# rtc.net
KiCad netlist of a schematic drawn in EAGLE
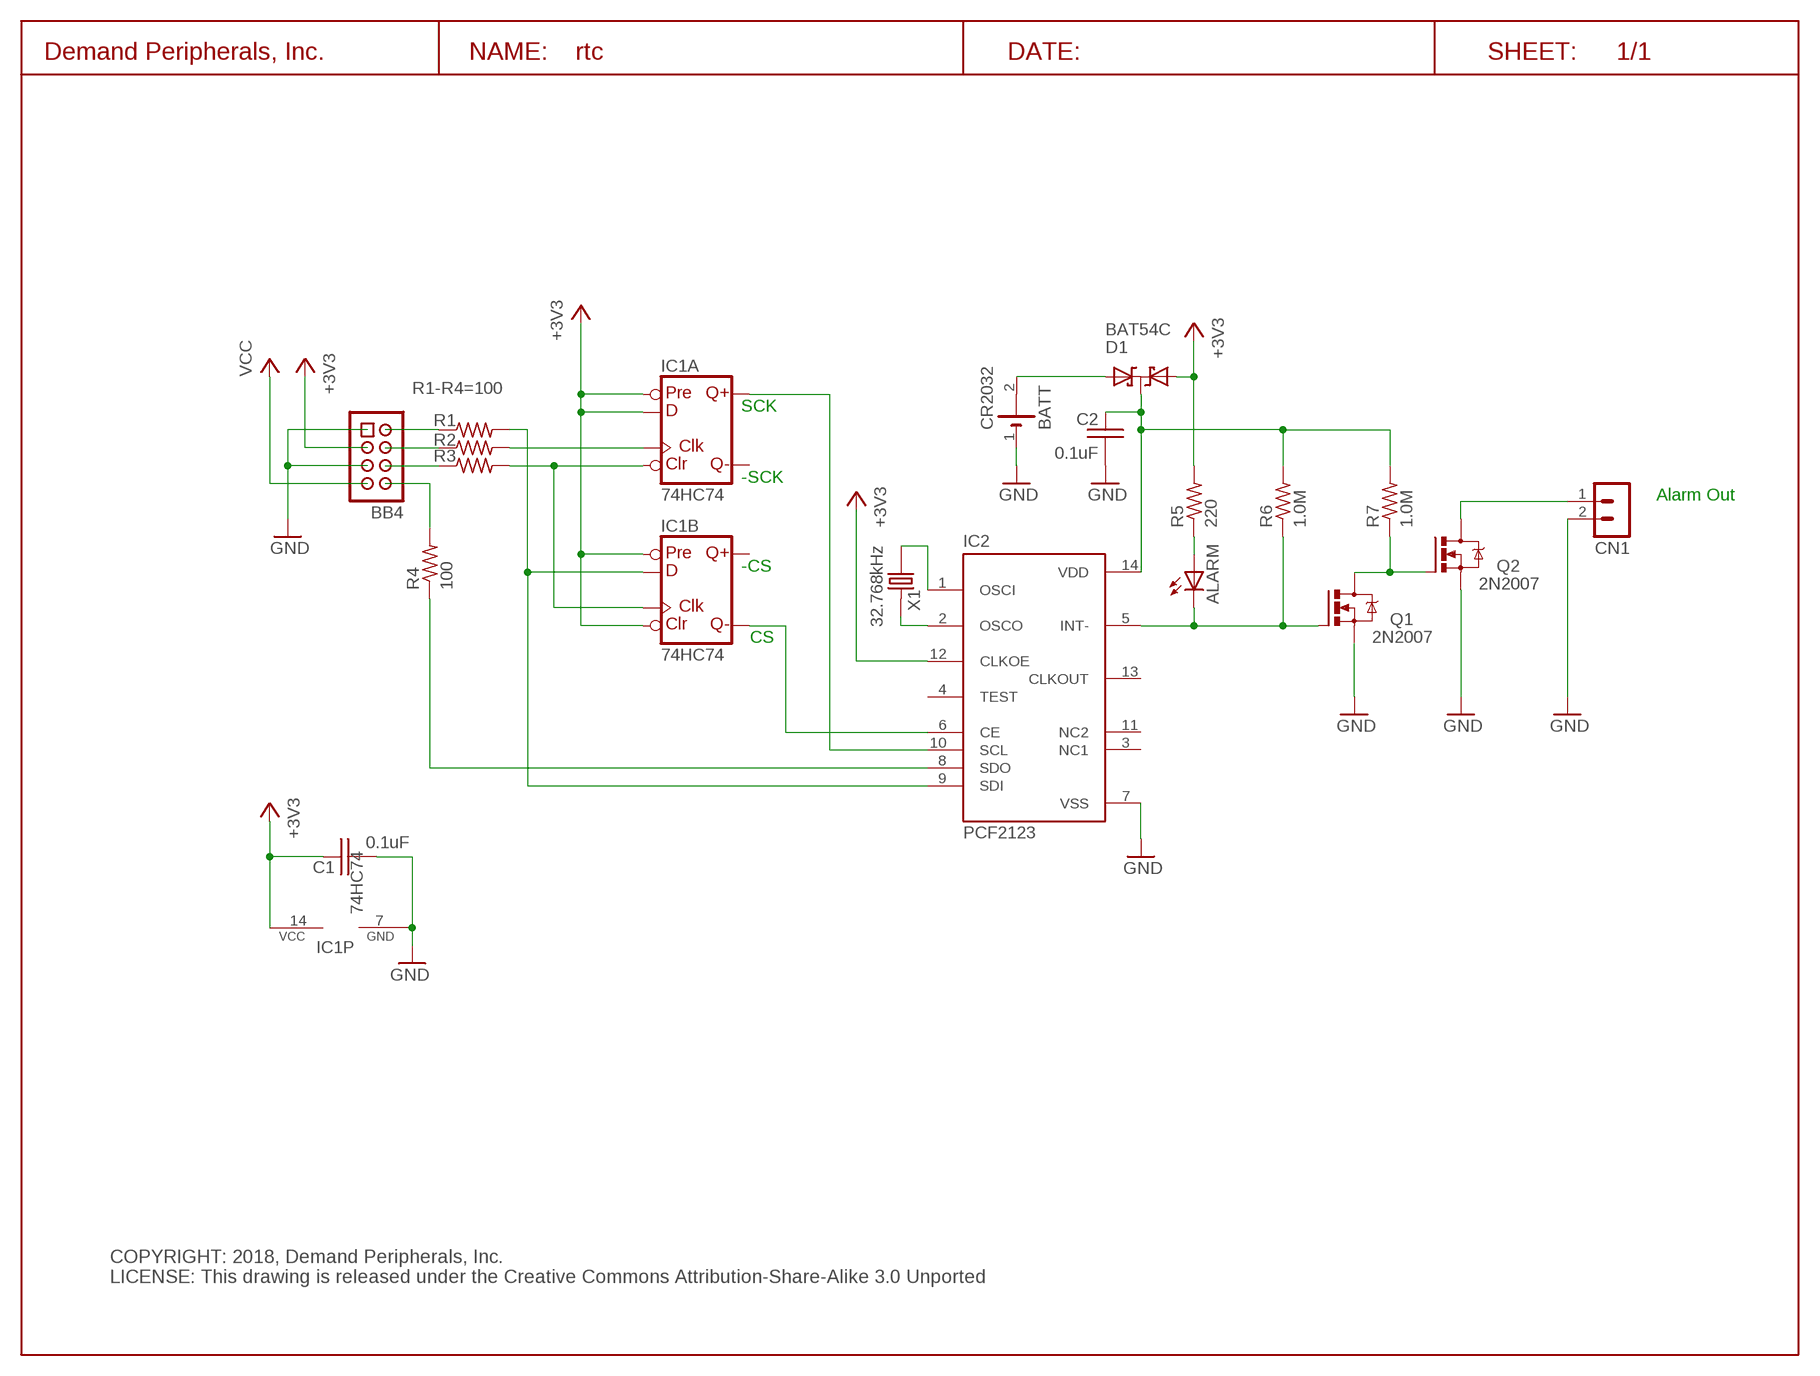
[diagram p0: schematic, sheet 1]

(export (version "E")
  (design (tool "Eeschema 10.0.6"))
  (components
    (comp (ref "ALARM")
      (value "Red_LED")
      (footprint "eagle-import:0805")
      (libsource (lib "eagle-import") (part "LED-0805-RED"))
    )
    (comp (ref "BATT")
      (value "CR2032")
      (footprint "eagle-import:CR2032_KEYSTONE")
      (libsource (lib "eagle-import") (part "CR2032_KEYSTONE"))
    )
    (comp (ref "BB4")
      (value "BB_CON")
      (footprint "eagle-import:HDR-4X2")
      (libsource (lib "eagle-import") (part "HDR-4X2-SHR"))
    )
    (comp (ref "C1")
      (value "0.1uF")
      (footprint "eagle-import:C0603")
      (libsource (lib "eagle-import") (part "C0.1UF_C0603"))
    )
    (comp (ref "C2")
      (value "0.1uF")
      (footprint "eagle-import:C0603")
      (libsource (lib "eagle-import") (part "C0.1UF_C0603"))
    )
    (comp (ref "CN1")
      (value "HDR-2X1-LCK")
      (footprint "eagle-import:HDR-2X1")
      (libsource (lib "eagle-import") (part "HDR-2X1-LCK"))
    )
    (comp (ref "D1")
      (value "BAT54C")
      (footprint "eagle-import:SOT23")
      (libsource (lib "eagle-import") (part "BAT54C"))
    )
    (comp (ref "IC1")
      (value "74HC74")
      (footprint "eagle-import:SO14")
      (libsource (lib "eagle-import") (part "74AHC74SS"))
    )
    (comp (ref "IC2")
      (value "PCF2123")
      (footprint "eagle-import:TSSOP14")
      (libsource (lib "eagle-import") (part "PCF2123"))
    )
    (comp (ref "Q1")
      (value "2N2007")
      (footprint "eagle-import:SOT23")
      (libsource (lib "eagle-import") (part "2N7002L"))
    )
    (comp (ref "Q2")
      (value "2N2007")
      (footprint "eagle-import:SOT23")
      (libsource (lib "eagle-import") (part "2N7002L"))
    )
    (comp (ref "R1")
      (value "100")
      (footprint "eagle-import:R0603")
      (libsource (lib "eagle-import") (part "R100_R0603"))
    )
    (comp (ref "R2")
      (value "100")
      (footprint "eagle-import:R0603")
      (libsource (lib "eagle-import") (part "R100_R0603"))
    )
    (comp (ref "R3")
      (value "100")
      (footprint "eagle-import:R0603")
      (libsource (lib "eagle-import") (part "R100_R0603"))
    )
    (comp (ref "R4")
      (value "100")
      (footprint "eagle-import:R0603")
      (libsource (lib "eagle-import") (part "R100_R0603"))
    )
    (comp (ref "R5")
      (value "220")
      (footprint "eagle-import:R0603")
      (libsource (lib "eagle-import") (part "R220_R0603"))
    )
    (comp (ref "R6")
      (value "1.0M")
      (footprint "eagle-import:R0603")
      (libsource (lib "eagle-import") (part "R1M_R0603"))
    )
    (comp (ref "R7")
      (value "1.0M")
      (footprint "eagle-import:R0603")
      (libsource (lib "eagle-import") (part "R1M_R0603"))
    )
    (comp (ref "U$1")
      (value "DP_FRAME_L")
      (footprint "eagle-import:LETTER_L")
      (libsource (lib "eagle-import") (part "DP_FRAME_L"))
    )
    (comp (ref "X1")
      (value "32.768kHz")
      (footprint "eagle-import:4-SOJ")
      (libsource (lib "eagle-import") (part "CRYSTAL-32.768"))
    )
  )
  (nets
    (net (code "1") (name "+3V3") (class "Default")
      (node (ref "BB4") (pin "3") (pinfunction "3_3") (pintype "passive"))
      (node (ref "C1") (pin "1") (pinfunction "1_1") (pintype "passive"))
      (node (ref "D1") (pin "2") (pinfunction "A_2") (pintype "passive"))
      (node (ref "IC1") (pin "10") (pinfunction "PRE_10") (pintype "input"))
      (node (ref "IC1") (pin "13") (pinfunction "CLR_13") (pintype "input"))
      (node (ref "IC1") (pin "14") (pinfunction "VCC_14") (pintype "power_in"))
      (node (ref "IC1") (pin "2") (pinfunction "D_2") (pintype "input"))
      (node (ref "IC1") (pin "4") (pinfunction "PRE_4") (pintype "input"))
      (node (ref "IC2") (pin "12") (pinfunction "CLKOE_12") (pintype "input"))
      (node (ref "R5") (pin "2") (pinfunction "2_2") (pintype "passive"))
    )
    (net (code "2") (name "GND") (class "Default")
      (node (ref "BATT") (pin "1") (pinfunction "-_1") (pintype "passive"))
      (node (ref "BB4") (pin "1") (pinfunction "1_1") (pintype "passive"))
      (node (ref "BB4") (pin "5") (pinfunction "5_5") (pintype "passive"))
      (node (ref "C1") (pin "2") (pinfunction "2_2") (pintype "passive"))
      (node (ref "C2") (pin "2") (pinfunction "2_2") (pintype "passive"))
      (node (ref "CN1") (pin "2") (pinfunction "1_2") (pintype "passive"))
      (node (ref "IC1") (pin "7") (pinfunction "GND_7") (pintype "power_in"))
      (node (ref "IC2") (pin "7") (pinfunction "VSS_7") (pintype "power_in"))
      (node (ref "Q1") (pin "3") (pinfunction "S_3") (pintype "passive"))
      (node (ref "Q2") (pin "3") (pinfunction "S_3") (pintype "passive"))
    )
    (net (code "3") (name "Net-(ALARM-PadA)") (class "Default")
      (node (ref "ALARM") (pin "A") (pinfunction "A_A") (pintype "passive"))
      (node (ref "R5") (pin "1") (pinfunction "1_1") (pintype "passive"))
    )
    (net (code "4") (name "Net-(BB4-Pad2)") (class "Default")
      (node (ref "BB4") (pin "2") (pinfunction "2_2") (pintype "passive"))
      (node (ref "R1") (pin "1") (pinfunction "1_1") (pintype "passive"))
    )
    (net (code "5") (name "Net-(BB4-Pad4)") (class "Default")
      (node (ref "BB4") (pin "4") (pinfunction "4_4") (pintype "passive"))
      (node (ref "R2") (pin "1") (pinfunction "1_1") (pintype "passive"))
    )
    (net (code "6") (name "Net-(BB4-Pad6)") (class "Default")
      (node (ref "BB4") (pin "6") (pinfunction "6_6") (pintype "passive"))
      (node (ref "R3") (pin "1") (pinfunction "1_1") (pintype "passive"))
    )
    (net (code "7") (name "Net-(BB4-Pad8)") (class "Default")
      (node (ref "BB4") (pin "8") (pinfunction "8_8") (pintype "passive"))
      (node (ref "R4") (pin "2") (pinfunction "2_2") (pintype "passive"))
    )
    (net (code "8") (name "Net-(CN1-2)") (class "Default")
      (node (ref "CN1") (pin "1") (pinfunction "2_1") (pintype "passive"))
      (node (ref "Q2") (pin "2") (pinfunction "D_2") (pintype "passive"))
    )
    (net (code "9") (name "Net-(D1-A1)") (class "Default")
      (node (ref "BATT") (pin "2") (pinfunction "+_2") (pintype "passive"))
      (node (ref "D1") (pin "1") (pinfunction "A1_1") (pintype "passive"))
    )
    (net (code "10") (name "Net-(D1-CC)") (class "Default")
      (node (ref "C2") (pin "1") (pinfunction "1_1") (pintype "passive"))
      (node (ref "D1") (pin "3") (pinfunction "CC_3") (pintype "passive"))
      (node (ref "IC2") (pin "14") (pinfunction "VDD_14") (pintype "power_in"))
      (node (ref "R6") (pin "2") (pinfunction "2_2") (pintype "passive"))
      (node (ref "R7") (pin "2") (pinfunction "2_2") (pintype "passive"))
    )
    (net (code "11") (name "Net-(IC1A-CLK)") (class "Default")
      (node (ref "IC1") (pin "3") (pinfunction "CLK_3") (pintype "input"))
      (node (ref "R2") (pin "2") (pinfunction "2_2") (pintype "passive"))
    )
    (net (code "12") (name "Net-(IC1A-CLR)") (class "Default")
      (node (ref "IC1") (pin "1") (pinfunction "CLR_1") (pintype "input"))
      (node (ref "IC1") (pin "11") (pinfunction "CLK_11") (pintype "input"))
      (node (ref "R3") (pin "2") (pinfunction "2_2") (pintype "passive"))
    )
    (net (code "13") (name "Net-(IC1A-Q)") (class "Default")
      (node (ref "IC1") (pin "5") (pinfunction "Q_5") (pintype "output"))
      (node (ref "IC2") (pin "10") (pinfunction "SCL_10") (pintype "input"))
    )
    (net (code "14") (name "Net-(IC1B-D)") (class "Default")
      (node (ref "IC1") (pin "12") (pinfunction "D_12") (pintype "input"))
      (node (ref "IC2") (pin "9") (pinfunction "SDI_9") (pintype "input"))
      (node (ref "R1") (pin "2") (pinfunction "2_2") (pintype "passive"))
    )
    (net (code "15") (name "Net-(IC1B-~{Q})") (class "Default")
      (node (ref "IC1") (pin "8") (pinfunction "~{Q}_8") (pintype "output"))
      (node (ref "IC2") (pin "6") (pinfunction "CE_6") (pintype "input"))
    )
    (net (code "16") (name "Net-(IC2-INT-)") (class "Default")
      (node (ref "ALARM") (pin "C") (pinfunction "C_C") (pintype "passive"))
      (node (ref "IC2") (pin "5") (pinfunction "INT-_5") (pintype "output"))
      (node (ref "Q1") (pin "1") (pinfunction "G_1") (pintype "passive"))
      (node (ref "R6") (pin "1") (pinfunction "1_1") (pintype "passive"))
    )
    (net (code "17") (name "Net-(IC2-OSCI)") (class "Default")
      (node (ref "IC2") (pin "1") (pinfunction "OSCI_1") (pintype "input"))
      (node (ref "X1") (pin "1") (pinfunction "1_1") (pintype "passive"))
    )
    (net (code "18") (name "Net-(IC2-OSCO)") (class "Default")
      (node (ref "IC2") (pin "2") (pinfunction "OSCO_2") (pintype "input"))
      (node (ref "X1") (pin "4") (pinfunction "2_4") (pintype "passive"))
    )
    (net (code "19") (name "Net-(IC2-SDO)") (class "Default")
      (node (ref "IC2") (pin "8") (pinfunction "SDO_8") (pintype "input"))
      (node (ref "R4") (pin "1") (pinfunction "1_1") (pintype "passive"))
    )
    (net (code "20") (name "Net-(Q1-D)") (class "Default")
      (node (ref "Q1") (pin "2") (pinfunction "D_2") (pintype "passive"))
      (node (ref "Q2") (pin "1") (pinfunction "G_1") (pintype "passive"))
      (node (ref "R7") (pin "1") (pinfunction "1_1") (pintype "passive"))
    )
    (net (code "21") (name "VCC") (class "Default")
      (node (ref "BB4") (pin "7") (pinfunction "7_7") (pintype "passive"))
    )
    (net (code "22") (name "unconnected-(BATT-+-Pad3)") (class "Default")
      (node (ref "BATT") (pin "3") (pinfunction "+_3") (pintype "passive"))
    )
    (net (code "23") (name "unconnected-(IC1A-~{Q}-Pad6)") (class "Default")
      (node (ref "IC1") (pin "6") (pinfunction "~{Q}_6") (pintype "output"))
    )
    (net (code "24") (name "unconnected-(IC1B-Q-Pad9)") (class "Default")
      (node (ref "IC1") (pin "9") (pinfunction "Q_9") (pintype "output"))
    )
    (net (code "25") (name "unconnected-(IC2-CLKOUT-Pad13)") (class "Default")
      (node (ref "IC2") (pin "13") (pinfunction "CLKOUT_13") (pintype "output"))
    )
    (net (code "26") (name "unconnected-(IC2-NC1-Pad3)") (class "Default")
      (node (ref "IC2") (pin "3") (pinfunction "NC1_3") (pintype "no_connect"))
    )
    (net (code "27") (name "unconnected-(IC2-NC2-Pad11)") (class "Default")
      (node (ref "IC2") (pin "11") (pinfunction "NC2_11") (pintype "no_connect"))
    )
    (net (code "28") (name "unconnected-(IC2-TEST-Pad4)") (class "Default")
      (node (ref "IC2") (pin "4") (pinfunction "TEST_4") (pintype "no_connect"))
    )
  )
)
